# Microcontroller_IO.net
KiCad netlist of a schematic drawn in Altium Designer
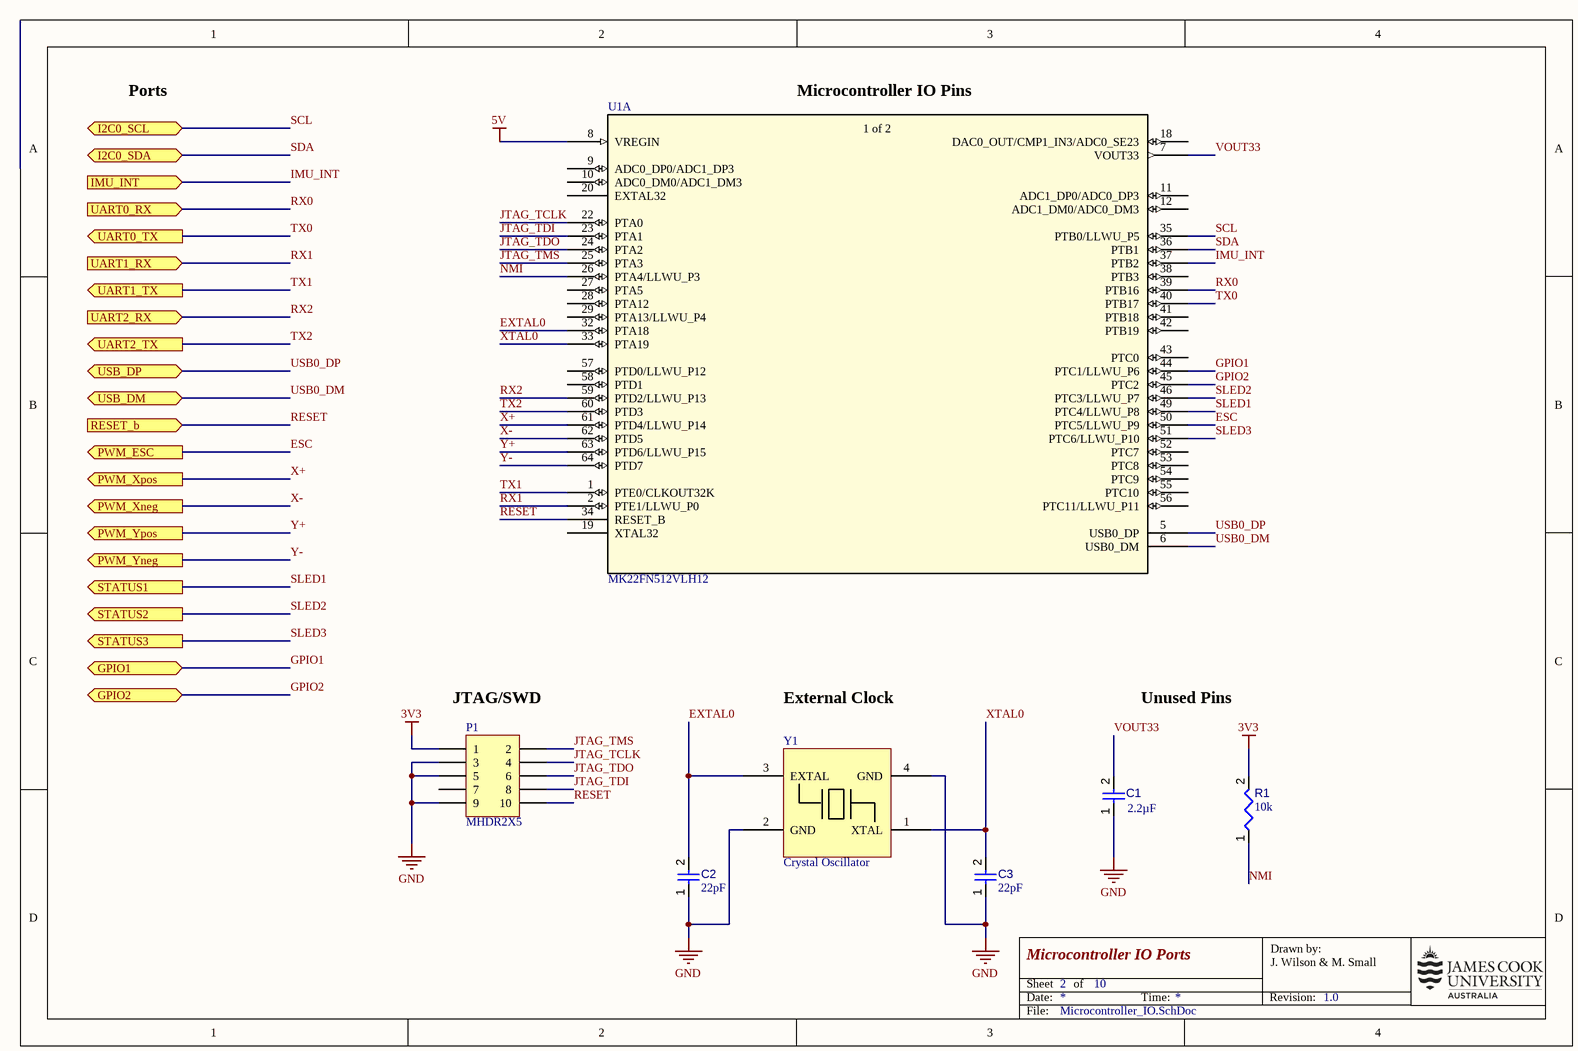
[diagram p0: Microcontroller_IO.SchDoc]

(export (version "E")
  (design (tool "Eeschema 10.0.6"))
  (components
    (comp (ref "C1")
      (value "2.2µF")
      (footprint "CAPC0805(2012)145_L")
      (description "Chip Capacitor, 2.2µF +/-20%, 10V, 0805, Thickness 1.45 mm")
      (fields (field (name "TOLERANCE") "10%") (field (name "Comment") "Capacitor 2.2µF +/-20% 10V 0805"))
      (libsource (lib "James Cook University") (part "CAP-NP-2"))
    )
    (comp (ref "C2")
      (value "22pF")
      (footprint "CAPC0805(2012)145_L")
      (description "Chip Capacitor, 22pF +/- 5%, 0805, Thickness 1.45 mm")
      (fields (field (name "TOLERANCE") "5%") (field (name "Comment") "Capacitor 22pF +/-5% 0805"))
      (libsource (lib "James Cook University") (part "CAP-NP-2"))
    )
    (comp (ref "C3")
      (value "22pF")
      (footprint "CAPC0805(2012)145_L")
      (description "Chip Capacitor, 22pF +/- 5%, 0805, Thickness 1.45 mm")
      (fields (field (name "TOLERANCE") "5%") (field (name "Comment") "Capacitor 22pF +/-5% 0805"))
      (libsource (lib "James Cook University") (part "CAP-NP-2"))
    )
    (comp (ref "P1")
      (value "MHDR2X5")
      (footprint "CC3501_Misc_Footprints:JTAG 2x5 1.27mm")
      (description "Header, 5-Pin, Dual row")
      (fields (field (name "PUBLISHER") "Altium Limited"))
      (libsource (lib "Miscellaneous Connectors") (part "MHDR2X5"))
    )
    (comp (ref "R1")
      (value "10k")
      (footprint "RESC0805(2012)_L")
      (description "Chip Resistor, 10 kOhms, +/-5%, 125 mW, -55 to 155 degC, 0805")
      (fields (field (name "POWER") "125mW") (field (name "TOLERANCE") "5%"))
      (libsource (lib "James Cook University") (part "RES-2"))
    )
    (comp (ref "U1")
      (value "MK22FN512VLH12")
      (footprint "LQFP-64_10X10X1.6_NXP")
      (description "No Description Available")
      (fields (field (name "COPYRIGHT") "Copyright (C) 2016 Accelerated Designs. All rights reserved"))
      (libsource (lib "MK22FN512VLH12") (part "MK22FN512VLH12"))
    )
    (comp (ref "Y1")
      (value "Crystal Oscillator")
      (footprint "CC3501_Misc_Footprints:ABM3B")
      (description "Abracon  ABM3B Oscillator")
      (libsource (lib "CC3501_Misc_Symbols") (part "Crystal Oscillator"))
    )
  )
  (nets
    (net (code "1") (name "/ESC") (class "Default")
      (node (ref "U1") (pin "50") (pinfunction "PTC5/LLWU_P9_50") (pintype "bidirectional"))
    )
    (net (code "2") (name "/EXTAL0") (class "Default")
      (node (ref "C2") (pin "2") (pinfunction "2_2") (pintype "passive"))
      (node (ref "U1") (pin "32") (pinfunction "PTA18_32") (pintype "bidirectional"))
      (node (ref "Y1") (pin "3") (pinfunction "EXTAL_3") (pintype "passive"))
    )
    (net (code "3") (name "/GPIO1") (class "Default")
      (node (ref "U1") (pin "44") (pinfunction "PTC1/LLWU_P6_44") (pintype "bidirectional"))
    )
    (net (code "4") (name "/GPIO2") (class "Default")
      (node (ref "U1") (pin "45") (pinfunction "PTC2_45") (pintype "bidirectional"))
    )
    (net (code "5") (name "/IMU_INT") (class "Default")
      (node (ref "U1") (pin "37") (pinfunction "PTB2_37") (pintype "bidirectional"))
    )
    (net (code "6") (name "/JTAG_TCLK") (class "Default")
      (node (ref "P1") (pin "4") (pinfunction "4_4") (pintype "passive"))
      (node (ref "U1") (pin "22") (pinfunction "PTA0_22") (pintype "bidirectional"))
    )
    (net (code "7") (name "/JTAG_TDI") (class "Default")
      (node (ref "P1") (pin "8") (pinfunction "8_8") (pintype "passive"))
      (node (ref "U1") (pin "23") (pinfunction "PTA1_23") (pintype "bidirectional"))
    )
    (net (code "8") (name "/JTAG_TDO") (class "Default")
      (node (ref "P1") (pin "6") (pinfunction "6_6") (pintype "passive"))
      (node (ref "U1") (pin "24") (pinfunction "PTA2_24") (pintype "bidirectional"))
    )
    (net (code "9") (name "/JTAG_TMS") (class "Default")
      (node (ref "P1") (pin "2") (pinfunction "2_2") (pintype "passive"))
      (node (ref "U1") (pin "25") (pinfunction "PTA3_25") (pintype "bidirectional"))
    )
    (net (code "10") (name "/NMI") (class "Default")
      (node (ref "R1") (pin "1") (pinfunction "1_1") (pintype "passive"))
      (node (ref "U1") (pin "26") (pinfunction "PTA4/LLWU_P3_26") (pintype "bidirectional"))
    )
    (net (code "11") (name "/RESET") (class "Default")
      (node (ref "P1") (pin "10") (pinfunction "10_10") (pintype "passive"))
      (node (ref "U1") (pin "34") (pinfunction "RESET_B_34") (pintype "passive"))
    )
    (net (code "12") (name "/RX0") (class "Default")
      (node (ref "U1") (pin "39") (pinfunction "PTB16_39") (pintype "bidirectional"))
    )
    (net (code "13") (name "/RX1") (class "Default")
      (node (ref "U1") (pin "2") (pinfunction "PTE1/LLWU_P0_2") (pintype "bidirectional"))
    )
    (net (code "14") (name "/RX2") (class "Default")
      (node (ref "U1") (pin "59") (pinfunction "PTD2/LLWU_P13_59") (pintype "bidirectional"))
    )
    (net (code "15") (name "/SCL") (class "Default")
      (node (ref "U1") (pin "35") (pinfunction "PTB0/LLWU_P5_35") (pintype "bidirectional"))
    )
    (net (code "16") (name "/SDA") (class "Default")
      (node (ref "U1") (pin "36") (pinfunction "PTB1_36") (pintype "bidirectional"))
    )
    (net (code "17") (name "/SLED1") (class "Default")
      (node (ref "U1") (pin "49") (pinfunction "PTC4/LLWU_P8_49") (pintype "bidirectional"))
    )
    (net (code "18") (name "/SLED2") (class "Default")
      (node (ref "U1") (pin "46") (pinfunction "PTC3/LLWU_P7_46") (pintype "bidirectional"))
    )
    (net (code "19") (name "/SLED3") (class "Default")
      (node (ref "U1") (pin "51") (pinfunction "PTC6/LLWU_P10_51") (pintype "bidirectional"))
    )
    (net (code "20") (name "/TX0") (class "Default")
      (node (ref "U1") (pin "40") (pinfunction "PTB17_40") (pintype "bidirectional"))
    )
    (net (code "21") (name "/TX1") (class "Default")
      (node (ref "U1") (pin "1") (pinfunction "PTE0/CLKOUT32K_1") (pintype "bidirectional"))
    )
    (net (code "22") (name "/TX2") (class "Default")
      (node (ref "U1") (pin "60") (pinfunction "PTD3_60") (pintype "bidirectional"))
    )
    (net (code "23") (name "/USB0_DM") (class "Default")
      (node (ref "U1") (pin "6") (pinfunction "USB0_DM_6") (pintype "passive"))
    )
    (net (code "24") (name "/USB0_DP") (class "Default")
      (node (ref "U1") (pin "5") (pinfunction "USB0_DP_5") (pintype "passive"))
    )
    (net (code "25") (name "/VOUT33") (class "Default")
      (node (ref "C1") (pin "2") (pinfunction "2_2") (pintype "passive"))
      (node (ref "U1") (pin "7") (pinfunction "VOUT33_7") (pintype "output"))
    )
    (net (code "26") (name "/X+") (class "Default")
      (node (ref "U1") (pin "61") (pinfunction "PTD4/LLWU_P14_61") (pintype "bidirectional"))
    )
    (net (code "27") (name "/X-") (class "Default")
      (node (ref "U1") (pin "62") (pinfunction "PTD5_62") (pintype "bidirectional"))
    )
    (net (code "28") (name "/XTAL0") (class "Default")
      (node (ref "C3") (pin "2") (pinfunction "2_2") (pintype "passive"))
      (node (ref "U1") (pin "33") (pinfunction "PTA19_33") (pintype "bidirectional"))
      (node (ref "Y1") (pin "1") (pinfunction "XTAL_1") (pintype "passive"))
    )
    (net (code "29") (name "/Y+") (class "Default")
      (node (ref "U1") (pin "63") (pinfunction "PTD6/LLWU_P15_63") (pintype "bidirectional"))
    )
    (net (code "30") (name "/Y-") (class "Default")
      (node (ref "U1") (pin "64") (pinfunction "PTD7_64") (pintype "bidirectional"))
    )
    (net (code "31") (name "3V3") (class "Default")
      (node (ref "P1") (pin "1") (pinfunction "1_1") (pintype "passive"))
      (node (ref "R1") (pin "2") (pinfunction "2_2") (pintype "passive"))
    )
    (net (code "32") (name "5V") (class "Default")
      (node (ref "U1") (pin "8") (pinfunction "VREGIN_8") (pintype "input"))
    )
    (net (code "33") (name "GND") (class "Default")
      (node (ref "C1") (pin "1") (pinfunction "1_1") (pintype "passive"))
      (node (ref "C2") (pin "1") (pinfunction "1_1") (pintype "passive"))
      (node (ref "C3") (pin "1") (pinfunction "1_1") (pintype "passive"))
      (node (ref "P1") (pin "3") (pinfunction "3_3") (pintype "passive"))
      (node (ref "P1") (pin "5") (pinfunction "5_5") (pintype "passive"))
      (node (ref "P1") (pin "9") (pinfunction "9_9") (pintype "passive"))
      (node (ref "Y1") (pin "2") (pinfunction "GND_2") (pintype "power_in"))
      (node (ref "Y1") (pin "4") (pinfunction "GND_4") (pintype "power_in"))
    )
    (net (code "34") (name "unconnected-(P1-Pad7)") (class "Default")
      (node (ref "P1") (pin "7") (pinfunction "7_7") (pintype "passive"))
    )
    (net (code "35") (name "unconnected-(U1A-ADC0_DM0{slash}ADC1_DM3-Pad10)") (class "Default")
      (node (ref "U1") (pin "10") (pinfunction "ADC0_DM0/ADC1_DM3_10") (pintype "bidirectional"))
    )
    (net (code "36") (name "unconnected-(U1A-ADC0_DP0{slash}ADC1_DP3-Pad9)") (class "Default")
      (node (ref "U1") (pin "9") (pinfunction "ADC0_DP0/ADC1_DP3_9") (pintype "bidirectional"))
    )
    (net (code "37") (name "unconnected-(U1A-ADC1_DM0{slash}ADC0_DM3-Pad12)") (class "Default")
      (node (ref "U1") (pin "12") (pinfunction "ADC1_DM0/ADC0_DM3_12") (pintype "bidirectional"))
    )
    (net (code "38") (name "unconnected-(U1A-ADC1_DP0{slash}ADC0_DP3-Pad11)") (class "Default")
      (node (ref "U1") (pin "11") (pinfunction "ADC1_DP0/ADC0_DP3_11") (pintype "bidirectional"))
    )
    (net (code "39") (name "unconnected-(U1A-DAC0_OUT{slash}CMP1_IN3{slash}ADC0_SE23-Pad18)") (class "Default")
      (node (ref "U1") (pin "18") (pinfunction "DAC0_OUT/CMP1_IN3/ADC0_SE23_18") (pintype "bidirectional"))
    )
    (net (code "40") (name "unconnected-(U1A-EXTAL32-Pad20)") (class "Default")
      (node (ref "U1") (pin "20") (pinfunction "EXTAL32_20") (pintype "passive"))
    )
    (net (code "41") (name "unconnected-(U1A-PTA5-Pad27)") (class "Default")
      (node (ref "U1") (pin "27") (pinfunction "PTA5_27") (pintype "bidirectional"))
    )
    (net (code "42") (name "unconnected-(U1A-PTA12-Pad28)") (class "Default")
      (node (ref "U1") (pin "28") (pinfunction "PTA12_28") (pintype "bidirectional"))
    )
    (net (code "43") (name "unconnected-(U1A-PTA13{slash}LLWU_P4-Pad29)") (class "Default")
      (node (ref "U1") (pin "29") (pinfunction "PTA13/LLWU_P4_29") (pintype "bidirectional"))
    )
    (net (code "44") (name "unconnected-(U1A-PTB3-Pad38)") (class "Default")
      (node (ref "U1") (pin "38") (pinfunction "PTB3_38") (pintype "bidirectional"))
    )
    (net (code "45") (name "unconnected-(U1A-PTB18-Pad41)") (class "Default")
      (node (ref "U1") (pin "41") (pinfunction "PTB18_41") (pintype "bidirectional"))
    )
    (net (code "46") (name "unconnected-(U1A-PTB19-Pad42)") (class "Default")
      (node (ref "U1") (pin "42") (pinfunction "PTB19_42") (pintype "bidirectional"))
    )
    (net (code "47") (name "unconnected-(U1A-PTC0-Pad43)") (class "Default")
      (node (ref "U1") (pin "43") (pinfunction "PTC0_43") (pintype "bidirectional"))
    )
    (net (code "48") (name "unconnected-(U1A-PTC7-Pad52)") (class "Default")
      (node (ref "U1") (pin "52") (pinfunction "PTC7_52") (pintype "bidirectional"))
    )
    (net (code "49") (name "unconnected-(U1A-PTC8-Pad53)") (class "Default")
      (node (ref "U1") (pin "53") (pinfunction "PTC8_53") (pintype "bidirectional"))
    )
    (net (code "50") (name "unconnected-(U1A-PTC9-Pad54)") (class "Default")
      (node (ref "U1") (pin "54") (pinfunction "PTC9_54") (pintype "bidirectional"))
    )
    (net (code "51") (name "unconnected-(U1A-PTC10-Pad55)") (class "Default")
      (node (ref "U1") (pin "55") (pinfunction "PTC10_55") (pintype "bidirectional"))
    )
    (net (code "52") (name "unconnected-(U1A-PTC11{slash}LLWU_P11-Pad56)") (class "Default")
      (node (ref "U1") (pin "56") (pinfunction "PTC11/LLWU_P11_56") (pintype "bidirectional"))
    )
    (net (code "53") (name "unconnected-(U1A-PTD0{slash}LLWU_P12-Pad57)") (class "Default")
      (node (ref "U1") (pin "57") (pinfunction "PTD0/LLWU_P12_57") (pintype "bidirectional"))
    )
    (net (code "54") (name "unconnected-(U1A-PTD1-Pad58)") (class "Default")
      (node (ref "U1") (pin "58") (pinfunction "PTD1_58") (pintype "bidirectional"))
    )
    (net (code "55") (name "unconnected-(U1A-XTAL32-Pad19)") (class "Default")
      (node (ref "U1") (pin "19") (pinfunction "XTAL32_19") (pintype "passive"))
    )
  )
)
